# fixture_auto-OSH.net
KiCad netlist of a schematic drawn in EAGLE
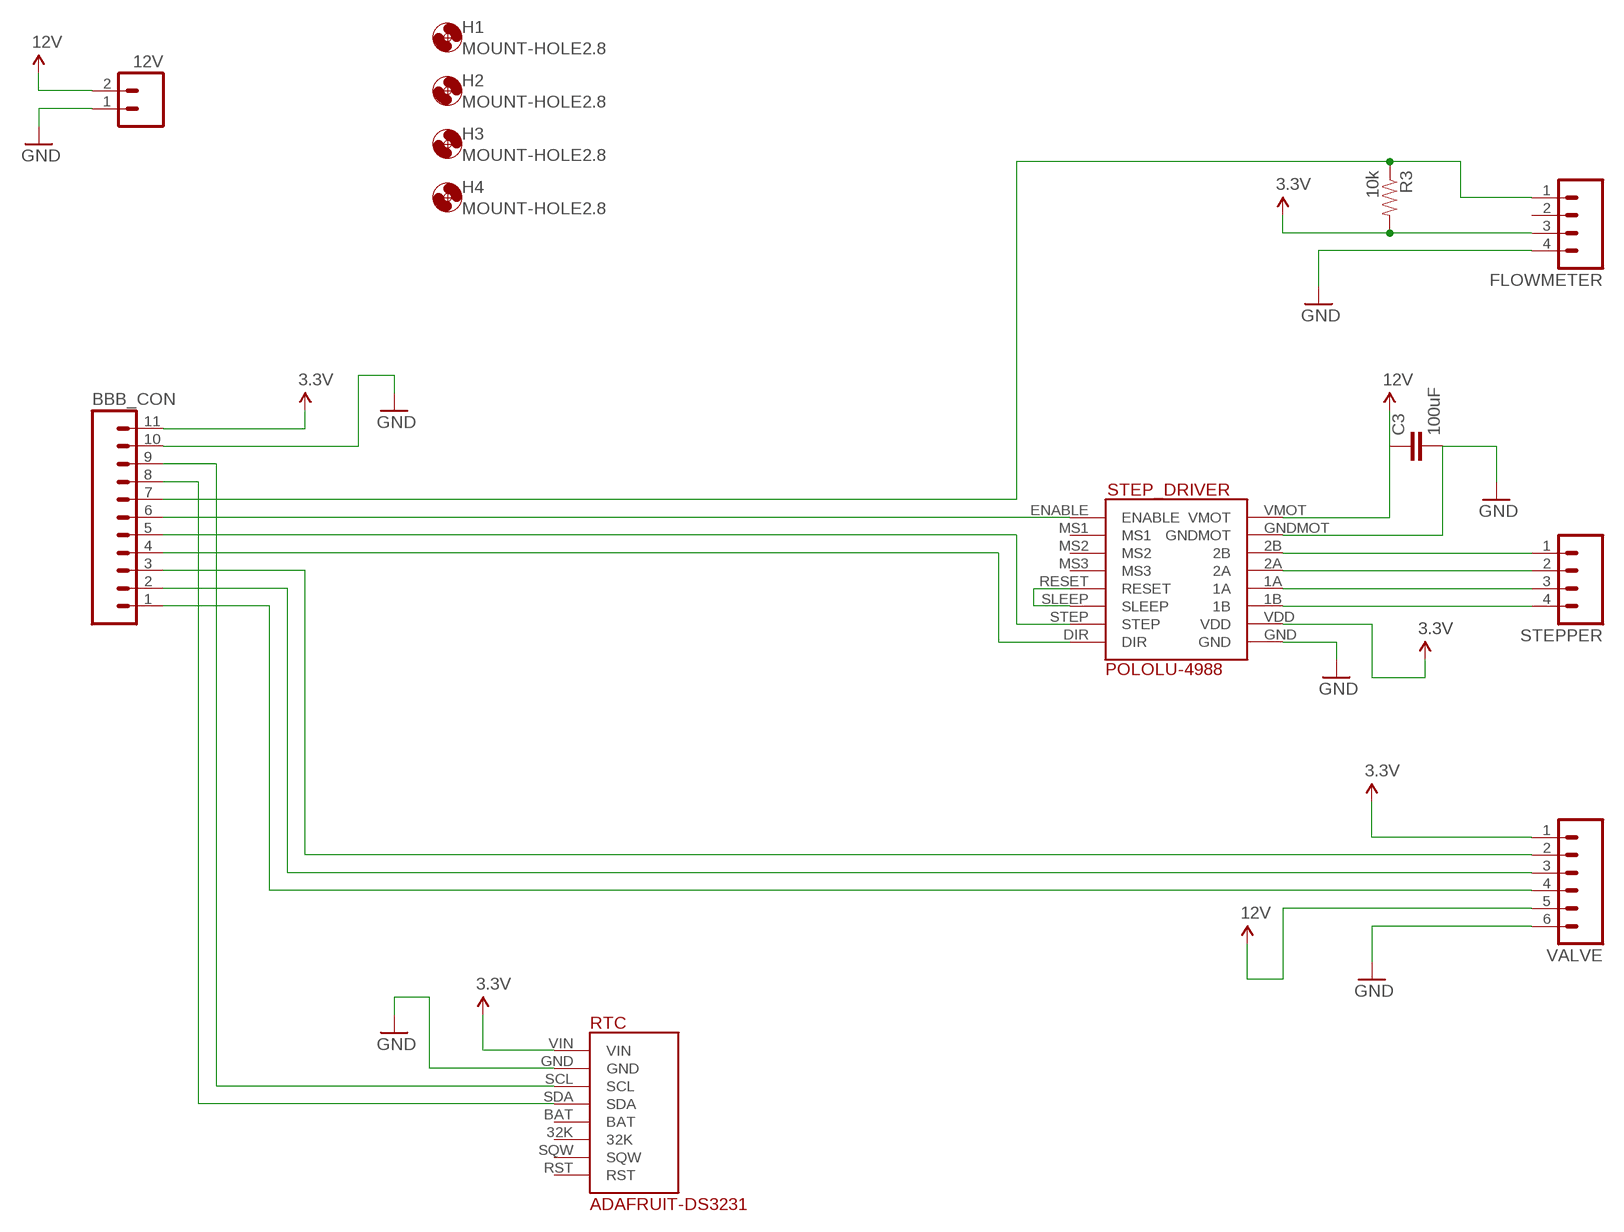
[diagram p0: schematic, sheet 1]

(export (version "E")
  (design (tool "Eeschema 10.0.6"))
  (components
    (comp (ref "12V")
      (value "M02LOCK_LONGPADS")
      (footprint "eagle-import:1X02_LOCK_LONGPADS")
      (libsource (lib "eagle-import") (part "M02LOCK_LONGPADS"))
    )
    (comp (ref "BBB_CON")
      (value "M11LOCK_LONGPADS")
      (footprint "eagle-import:1X11_LOCK_LONGPADS")
      (libsource (lib "eagle-import") (part "M11LOCK_LONGPADS"))
    )
    (comp (ref "C3")
      (value "100uF")
      (footprint "eagle-import:CAP-PTH-SMALL-KIT")
      (libsource (lib "eagle-import") (part "0.1UF-50V-20%(PTH)KIT-EZ"))
    )
    (comp (ref "FLOWMETER")
      (value "M04LOCK_LONGPADS")
      (footprint "eagle-import:1X04_LOCK_LONGPADS")
      (libsource (lib "eagle-import") (part "M04LOCK_LONGPADS"))
    )
    (comp (ref "H1")
      (value "MOUNT-HOLE2.8")
      (footprint "eagle-import:2,8")
      (libsource (lib "eagle-import") (part "MOUNT-HOLE2.8"))
    )
    (comp (ref "H2")
      (value "MOUNT-HOLE2.8")
      (footprint "eagle-import:2,8")
      (libsource (lib "eagle-import") (part "MOUNT-HOLE2.8"))
    )
    (comp (ref "H3")
      (value "MOUNT-HOLE2.8")
      (footprint "eagle-import:2,8")
      (libsource (lib "eagle-import") (part "MOUNT-HOLE2.8"))
    )
    (comp (ref "H4")
      (value "MOUNT-HOLE2.8")
      (footprint "eagle-import:2,8")
      (libsource (lib "eagle-import") (part "MOUNT-HOLE2.8"))
    )
    (comp (ref "R3")
      (value "10k")
      (footprint "eagle-import:AXIAL-0.3EZ")
      (libsource (lib "eagle-import") (part "RESISTOREZ"))
    )
    (comp (ref "RTC")
      (value "ADAFRUIT-DS3231")
      (footprint "eagle-import:ADAFRUIT-DS3231")
      (libsource (lib "eagle-import") (part "ADAFRUIT-DS3231"))
    )
    (comp (ref "STEPPER")
      (value "M04LOCK_LONGPADS")
      (footprint "eagle-import:1X04_LOCK_LONGPADS")
      (libsource (lib "eagle-import") (part "M04LOCK_LONGPADS"))
    )
    (comp (ref "STEP_DRIVER")
      (value "POLOLU-4988")
      (footprint "eagle-import:POLOLU-4988")
      (libsource (lib "eagle-import") (part "POLOLU-4988"))
    )
    (comp (ref "VALVE")
      (value "M06LOCK_LONGPADS")
      (footprint "eagle-import:1X06_LOCK_LONGPADS")
      (libsource (lib "eagle-import") (part "M06LOCK_LONGPADS"))
    )
  )
  (nets
    (net (code "1") (name "3.3V") (class "Default")
      (node (ref "BBB_CON") (pin "11") (pinfunction "11_11") (pintype "passive"))
      (node (ref "FLOWMETER") (pin "3") (pinfunction "3_3") (pintype "passive"))
      (node (ref "R3") (pin "P$2") (pinfunction "2_P$2") (pintype "passive"))
      (node (ref "RTC") (pin "VIN") (pinfunction "VIN_VIN") (pintype "bidirectional"))
      (node (ref "STEP_DRIVER") (pin "VDD") (pinfunction "VDD_VDD") (pintype "bidirectional"))
      (node (ref "VALVE") (pin "1") (pinfunction "1_1") (pintype "passive"))
    )
    (net (code "2") (name "12V") (class "Default")
      (node (ref "12V") (pin "2") (pinfunction "2_2") (pintype "passive"))
      (node (ref "C3") (pin "1") (pinfunction "1_1") (pintype "passive"))
      (node (ref "STEP_DRIVER") (pin "VMOT") (pinfunction "VMOT_VMOT") (pintype "bidirectional"))
      (node (ref "VALVE") (pin "5") (pinfunction "5_5") (pintype "passive"))
    )
    (net (code "3") (name "GND") (class "Default")
      (node (ref "12V") (pin "1") (pinfunction "1_1") (pintype "passive"))
      (node (ref "BBB_CON") (pin "10") (pinfunction "10_10") (pintype "passive"))
      (node (ref "C3") (pin "2") (pinfunction "2_2") (pintype "passive"))
      (node (ref "FLOWMETER") (pin "4") (pinfunction "4_4") (pintype "passive"))
      (node (ref "RTC") (pin "GND") (pinfunction "GND_GND") (pintype "bidirectional"))
      (node (ref "STEP_DRIVER") (pin "GND") (pinfunction "GND_GND") (pintype "bidirectional"))
      (node (ref "STEP_DRIVER") (pin "GNDMOT") (pinfunction "GNDMOT_GNDMOT") (pintype "bidirectional"))
      (node (ref "VALVE") (pin "6") (pinfunction "6_6") (pintype "passive"))
    )
    (net (code "4") (name "Net-(BBB_CON-Pad1)") (class "Default")
      (node (ref "BBB_CON") (pin "1") (pinfunction "1_1") (pintype "passive"))
      (node (ref "VALVE") (pin "4") (pinfunction "4_4") (pintype "passive"))
    )
    (net (code "5") (name "Net-(BBB_CON-Pad2)") (class "Default")
      (node (ref "BBB_CON") (pin "2") (pinfunction "2_2") (pintype "passive"))
      (node (ref "VALVE") (pin "3") (pinfunction "3_3") (pintype "passive"))
    )
    (net (code "6") (name "Net-(BBB_CON-Pad3)") (class "Default")
      (node (ref "BBB_CON") (pin "3") (pinfunction "3_3") (pintype "passive"))
      (node (ref "VALVE") (pin "2") (pinfunction "2_2") (pintype "passive"))
    )
    (net (code "7") (name "Net-(BBB_CON-Pad4)") (class "Default")
      (node (ref "BBB_CON") (pin "4") (pinfunction "4_4") (pintype "passive"))
      (node (ref "STEP_DRIVER") (pin "DIR") (pinfunction "DIR_DIR") (pintype "bidirectional"))
    )
    (net (code "8") (name "Net-(BBB_CON-Pad5)") (class "Default")
      (node (ref "BBB_CON") (pin "5") (pinfunction "5_5") (pintype "passive"))
      (node (ref "STEP_DRIVER") (pin "STEP") (pinfunction "STEP_STEP") (pintype "bidirectional"))
    )
    (net (code "9") (name "Net-(BBB_CON-Pad6)") (class "Default")
      (node (ref "BBB_CON") (pin "6") (pinfunction "6_6") (pintype "passive"))
      (node (ref "STEP_DRIVER") (pin "ENABLE") (pinfunction "ENABLE_ENABLE") (pintype "bidirectional"))
    )
    (net (code "10") (name "Net-(BBB_CON-Pad8)") (class "Default")
      (node (ref "BBB_CON") (pin "8") (pinfunction "8_8") (pintype "passive"))
      (node (ref "RTC") (pin "SDA") (pinfunction "SDA_SDA") (pintype "bidirectional"))
    )
    (net (code "11") (name "Net-(BBB_CON-Pad9)") (class "Default")
      (node (ref "BBB_CON") (pin "9") (pinfunction "9_9") (pintype "passive"))
      (node (ref "RTC") (pin "SCL") (pinfunction "SCL_SCL") (pintype "bidirectional"))
    )
    (net (code "12") (name "Net-(R3-1)") (class "Default")
      (node (ref "BBB_CON") (pin "7") (pinfunction "7_7") (pintype "passive"))
      (node (ref "FLOWMETER") (pin "1") (pinfunction "1_1") (pintype "passive"))
      (node (ref "R3") (pin "P$1") (pinfunction "1_P$1") (pintype "passive"))
    )
    (net (code "13") (name "Net-(STEPPER-Pad1)") (class "Default")
      (node (ref "STEPPER") (pin "1") (pinfunction "1_1") (pintype "passive"))
      (node (ref "STEP_DRIVER") (pin "2B") (pinfunction "2B_2B") (pintype "bidirectional"))
    )
    (net (code "14") (name "Net-(STEPPER-Pad2)") (class "Default")
      (node (ref "STEPPER") (pin "2") (pinfunction "2_2") (pintype "passive"))
      (node (ref "STEP_DRIVER") (pin "2A") (pinfunction "2A_2A") (pintype "bidirectional"))
    )
    (net (code "15") (name "Net-(STEPPER-Pad3)") (class "Default")
      (node (ref "STEPPER") (pin "3") (pinfunction "3_3") (pintype "passive"))
      (node (ref "STEP_DRIVER") (pin "1A") (pinfunction "1A_1A") (pintype "bidirectional"))
    )
    (net (code "16") (name "Net-(STEPPER-Pad4)") (class "Default")
      (node (ref "STEPPER") (pin "4") (pinfunction "4_4") (pintype "passive"))
      (node (ref "STEP_DRIVER") (pin "1B") (pinfunction "1B_1B") (pintype "bidirectional"))
    )
    (net (code "17") (name "Net-(STEP_DRIVER-PadRESET)") (class "Default")
      (node (ref "STEP_DRIVER") (pin "RESET") (pinfunction "RESET_RESET") (pintype "bidirectional"))
      (node (ref "STEP_DRIVER") (pin "SLEEP") (pinfunction "SLEEP_SLEEP") (pintype "bidirectional"))
    )
    (net (code "18") (name "unconnected-(FLOWMETER-Pad2)") (class "Default")
      (node (ref "FLOWMETER") (pin "2") (pinfunction "2_2") (pintype "passive"))
    )
    (net (code "19") (name "unconnected-(RTC-Pad32K)") (class "Default")
      (node (ref "RTC") (pin "32K") (pinfunction "32K_32K") (pintype "bidirectional"))
    )
    (net (code "20") (name "unconnected-(RTC-PadBAT)") (class "Default")
      (node (ref "RTC") (pin "BAT") (pinfunction "BAT_BAT") (pintype "bidirectional"))
    )
    (net (code "21") (name "unconnected-(RTC-PadRST)") (class "Default")
      (node (ref "RTC") (pin "RST") (pinfunction "RST_RST") (pintype "bidirectional"))
    )
    (net (code "22") (name "unconnected-(RTC-PadSQW)") (class "Default")
      (node (ref "RTC") (pin "SQW") (pinfunction "SQW_SQW") (pintype "bidirectional"))
    )
    (net (code "23") (name "unconnected-(STEP_DRIVER-PadMS1)") (class "Default")
      (node (ref "STEP_DRIVER") (pin "MS1") (pinfunction "MS1_MS1") (pintype "bidirectional"))
    )
    (net (code "24") (name "unconnected-(STEP_DRIVER-PadMS2)") (class "Default")
      (node (ref "STEP_DRIVER") (pin "MS2") (pinfunction "MS2_MS2") (pintype "bidirectional"))
    )
    (net (code "25") (name "unconnected-(STEP_DRIVER-PadMS3)") (class "Default")
      (node (ref "STEP_DRIVER") (pin "MS3") (pinfunction "MS3_MS3") (pintype "bidirectional"))
    )
  )
)
